# Peripherals.net
KiCad netlist of a schematic drawn in Altium Designer
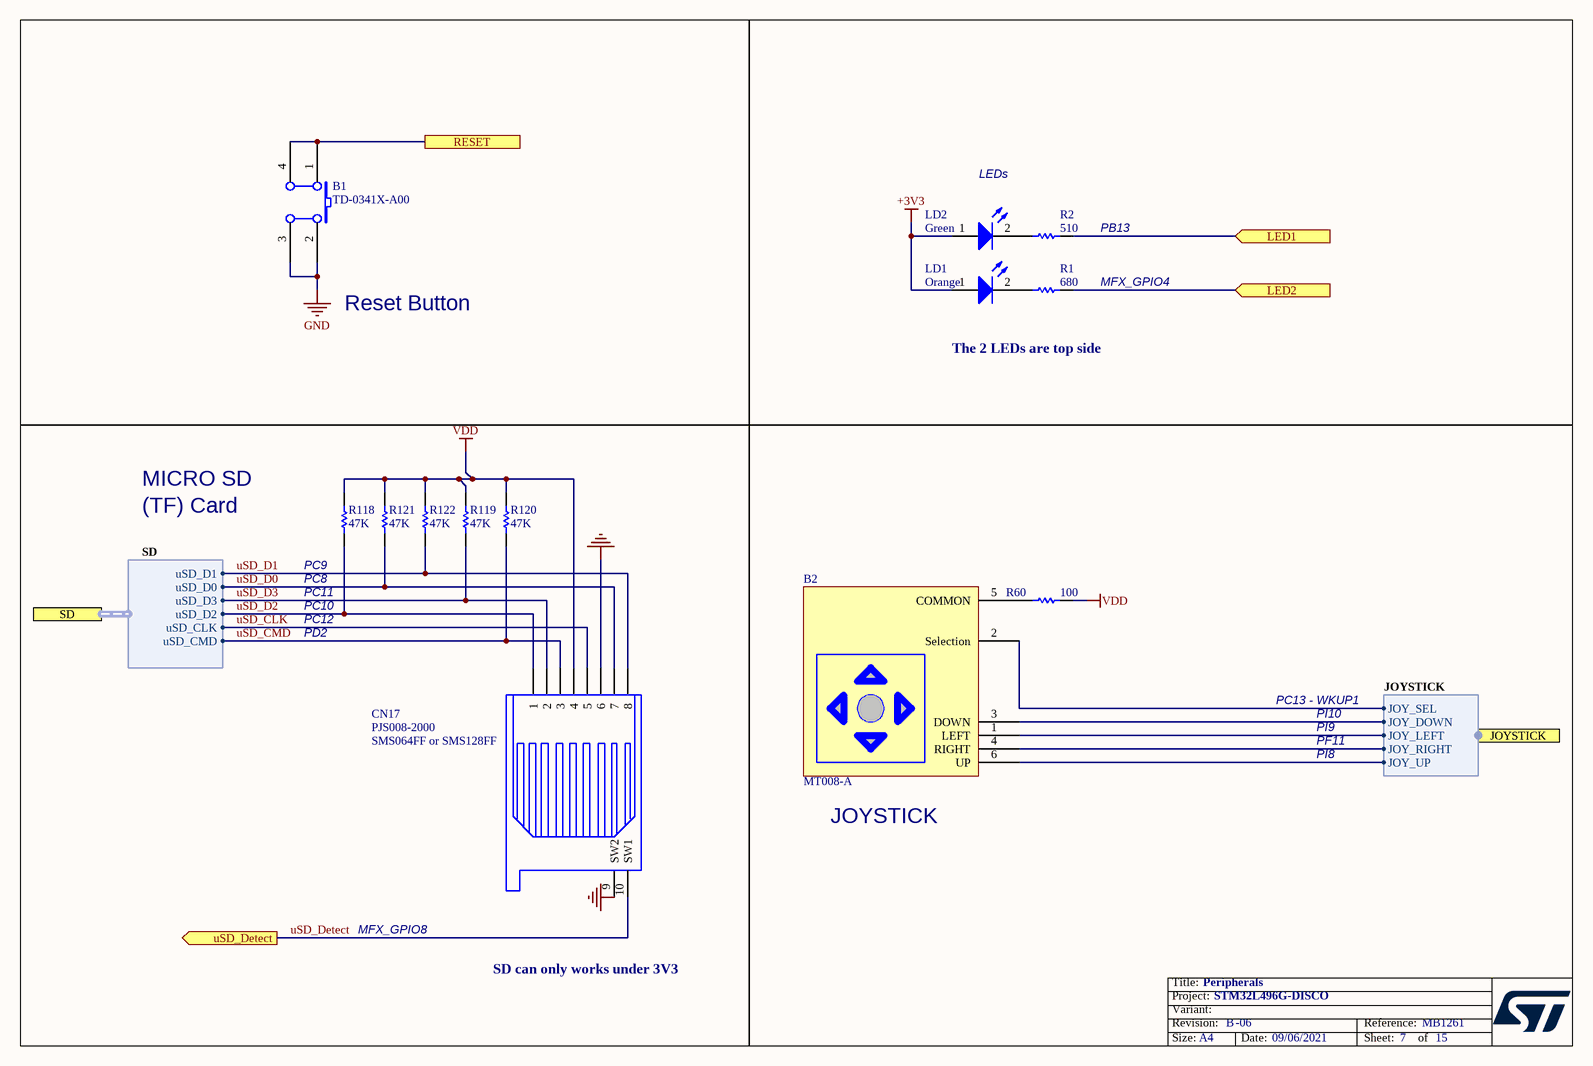
[diagram p0: Peripherals.SchDoc]

(export (version "E")
  (design (tool "Eeschema 10.0.6"))
  (components
    (comp (ref "B1")
      (value "TD-0341X-A00")
      (footprint "PB10")
      (description "SE Push Button TD-0341 [RESET/Black]")
      (libsource (lib "Documents") (part "SW PUSHBUTTON"))
    )
    (comp (ref "B2")
      (value "MT008-A")
      (footprint "MT-008A")
      (description "Joystick")
      (libsource (lib "MB1209_2") (part "MT-008A"))
    )
    (comp (ref "CN17")
      (value "PJS008-2000")
      (footprint "MSD_PJS008_")
      (libsource (lib "MB525") (part "SMS016AFA5E"))
    )
    (comp (ref "LD1")
      (value "19-217/S2C-AM2N2VY/3T")
      (footprint "0603D")
      (description "LED,Orange,0603")
      (fields (field (name "CORLOR") "Orange") (field (name "PUBLISHER") "Altium Limited"))
      (libsource (lib "Miscellaneous Devices") (part "LED2"))
    )
    (comp (ref "LD2")
      (value "19-213SY6C/S530-E2/TR8LED")
      (footprint "0603D")
      (description "LED,Green,0603")
      (fields (field (name "CORLOR") "Green") (field (name "PUBLISHER") "Altium Limited"))
      (libsource (lib "Miscellaneous Devices") (part "LED2"))
    )
    (comp (ref "R1")
      (value "680")
      (footprint "0603R")
      (description "Resistor,680R,0603,1%,YAGEO")
      (fields (field (name "Comment") "RC0603FR-07680RL") (field (name "PUBLISHER") "Altium Limited"))
      (libsource (lib "Miscellaneous Devices") (part "res1"))
    )
    (comp (ref "R2")
      (value "510")
      (footprint "0603R")
      (description "Resistor,510R,0603,1%,YAGEO")
      (fields (field (name "Comment") "RC0603FR-07510RL") (field (name "PUBLISHER") "Altium Limited"))
      (libsource (lib "Miscellaneous Devices") (part "res1"))
    )
    (comp (ref "R60")
      (value "100")
      (footprint "0603R")
      (description "Resistor, 100 ,0603,1%,YAGEO")
      (fields (field (name "Comment") "RC0603JR-07100RL") (field (name "PUBLISHER") "Altium Limited"))
      (libsource (lib "Miscellaneous Devices") (part "res1"))
    )
    (comp (ref "R118")
      (value "47K")
      (footprint "0603R")
      (description "Resistor,47K,0603,1%,YAGEO")
      (fields (field (name "PUBLISHER") "Altium Limited"))
      (libsource (lib "Miscellaneous Devices") (part "res1"))
    )
    (comp (ref "R119")
      (value "47K")
      (footprint "0603R")
      (description "Resistor,47K,0603,1%,YAGEO")
      (fields (field (name "PUBLISHER") "Altium Limited"))
      (libsource (lib "Miscellaneous Devices") (part "res1"))
    )
    (comp (ref "R120")
      (value "47K")
      (footprint "0603R")
      (description "Resistor,47K,0603,1%,YAGEO")
      (fields (field (name "PUBLISHER") "Altium Limited"))
      (libsource (lib "Miscellaneous Devices") (part "res1"))
    )
    (comp (ref "R121")
      (value "47K")
      (footprint "0603R")
      (description "Resistor,47K,0603,1%,YAGEO")
      (fields (field (name "PUBLISHER") "Altium Limited"))
      (libsource (lib "Miscellaneous Devices") (part "res1"))
    )
    (comp (ref "R122")
      (value "47K")
      (footprint "0603R")
      (description "Resistor,47K,0603,1%,YAGEO")
      (fields (field (name "PUBLISHER") "Altium Limited"))
      (libsource (lib "Miscellaneous Devices") (part "res1"))
    )
  )
  (nets
    (net (code "3") (name "+3V3") (class "Default")
      (node (ref "LD1") (pin "1") (pinfunction "A_1") (pintype "passive"))
      (node (ref "LD2") (pin "1") (pinfunction "A_1") (pintype "passive"))
    )
    (net (code "4") (name "/JOY_DOWN") (class "Default")
      (node (ref "B2") (pin "3") (pinfunction "DOWN_3") (pintype "passive"))
    )
    (net (code "5") (name "/JOY_LEFT") (class "Default")
      (node (ref "B2") (pin "1") (pinfunction "LEFT_1") (pintype "passive"))
    )
    (net (code "6") (name "/JOY_RIGHT") (class "Default")
      (node (ref "B2") (pin "4") (pinfunction "RIGHT_4") (pintype "passive"))
    )
    (net (code "7") (name "/JOY_SEL") (class "Default")
      (node (ref "B2") (pin "2") (pinfunction "Selection_2") (pintype "passive"))
    )
    (net (code "8") (name "/JOY_UP") (class "Default")
      (node (ref "B2") (pin "6") (pinfunction "UP_6") (pintype "passive"))
    )
    (net (code "9") (name "/LED1") (class "Default")
      (node (ref "R2") (pin "1") (pinfunction "1_1") (pintype "passive"))
    )
    (net (code "10") (name "/LED2") (class "Default")
      (node (ref "R1") (pin "1") (pinfunction "1_1") (pintype "passive"))
    )
    (net (code "11") (name "/RESET") (class "Default")
      (node (ref "B1") (pin "1") (pinfunction "A0_1") (pintype "passive"))
      (node (ref "B1") (pin "4") (pinfunction "A1_4") (pintype "passive"))
    )
    (net (code "12") (name "/uSD_CLK") (class "Default")
      (node (ref "CN17") (pin "5") (pinfunction "5_5") (pintype "passive"))
    )
    (net (code "13") (name "/uSD_CMD") (class "Default")
      (node (ref "CN17") (pin "3") (pinfunction "3_3") (pintype "passive"))
      (node (ref "R120") (pin "1") (pinfunction "1_1") (pintype "passive"))
    )
    (net (code "14") (name "/uSD_D0") (class "Default")
      (node (ref "CN17") (pin "7") (pinfunction "7_7") (pintype "passive"))
      (node (ref "R121") (pin "1") (pinfunction "1_1") (pintype "passive"))
    )
    (net (code "15") (name "/uSD_D1") (class "Default")
      (node (ref "CN17") (pin "8") (pinfunction "8_8") (pintype "passive"))
      (node (ref "R122") (pin "1") (pinfunction "1_1") (pintype "passive"))
    )
    (net (code "16") (name "/uSD_D2") (class "Default")
      (node (ref "CN17") (pin "1") (pinfunction "1_1") (pintype "passive"))
      (node (ref "R118") (pin "1") (pinfunction "1_1") (pintype "passive"))
    )
    (net (code "17") (name "/uSD_D3") (class "Default")
      (node (ref "CN17") (pin "2") (pinfunction "2_2") (pintype "passive"))
      (node (ref "R119") (pin "1") (pinfunction "1_1") (pintype "passive"))
    )
    (net (code "18") (name "/uSD_Detect") (class "Default")
      (node (ref "CN17") (pin "10") (pinfunction "SW1_10") (pintype "passive"))
    )
    (net (code "21") (name "GND") (class "Default")
      (node (ref "B1") (pin "2") (pinfunction "B0_2") (pintype "passive"))
      (node (ref "B1") (pin "3") (pinfunction "B1_3") (pintype "passive"))
      (node (ref "CN17") (pin "6") (pinfunction "6_6") (pintype "passive"))
      (node (ref "CN17") (pin "9") (pinfunction "SW2_9") (pintype "passive"))
    )
    (net (code "22") (name "Net-(B2-COMMON)") (class "Default")
      (node (ref "B2") (pin "5") (pinfunction "COMMON_5") (pintype "passive"))
      (node (ref "R60") (pin "2") (pinfunction "2_2") (pintype "passive"))
    )
    (net (code "23") (name "Net-(LD1-K)") (class "Default")
      (node (ref "LD1") (pin "2") (pinfunction "K_2") (pintype "passive"))
      (node (ref "R1") (pin "2") (pinfunction "2_2") (pintype "passive"))
    )
    (net (code "24") (name "Net-(LD2-K)") (class "Default")
      (node (ref "LD2") (pin "2") (pinfunction "K_2") (pintype "passive"))
      (node (ref "R2") (pin "2") (pinfunction "2_2") (pintype "passive"))
    )
    (net (code "25") (name "VDD") (class "Default")
      (node (ref "CN17") (pin "4") (pinfunction "4_4") (pintype "passive"))
      (node (ref "R118") (pin "2") (pinfunction "2_2") (pintype "passive"))
      (node (ref "R119") (pin "2") (pinfunction "2_2") (pintype "passive"))
      (node (ref "R120") (pin "2") (pinfunction "2_2") (pintype "passive"))
      (node (ref "R121") (pin "2") (pinfunction "2_2") (pintype "passive"))
      (node (ref "R122") (pin "2") (pinfunction "2_2") (pintype "passive"))
      (node (ref "R60") (pin "1") (pinfunction "1_1") (pintype "passive"))
    )
  )
)
